# ORD_PT2399.net
KiCad netlist of a schematic drawn in Altium Designer
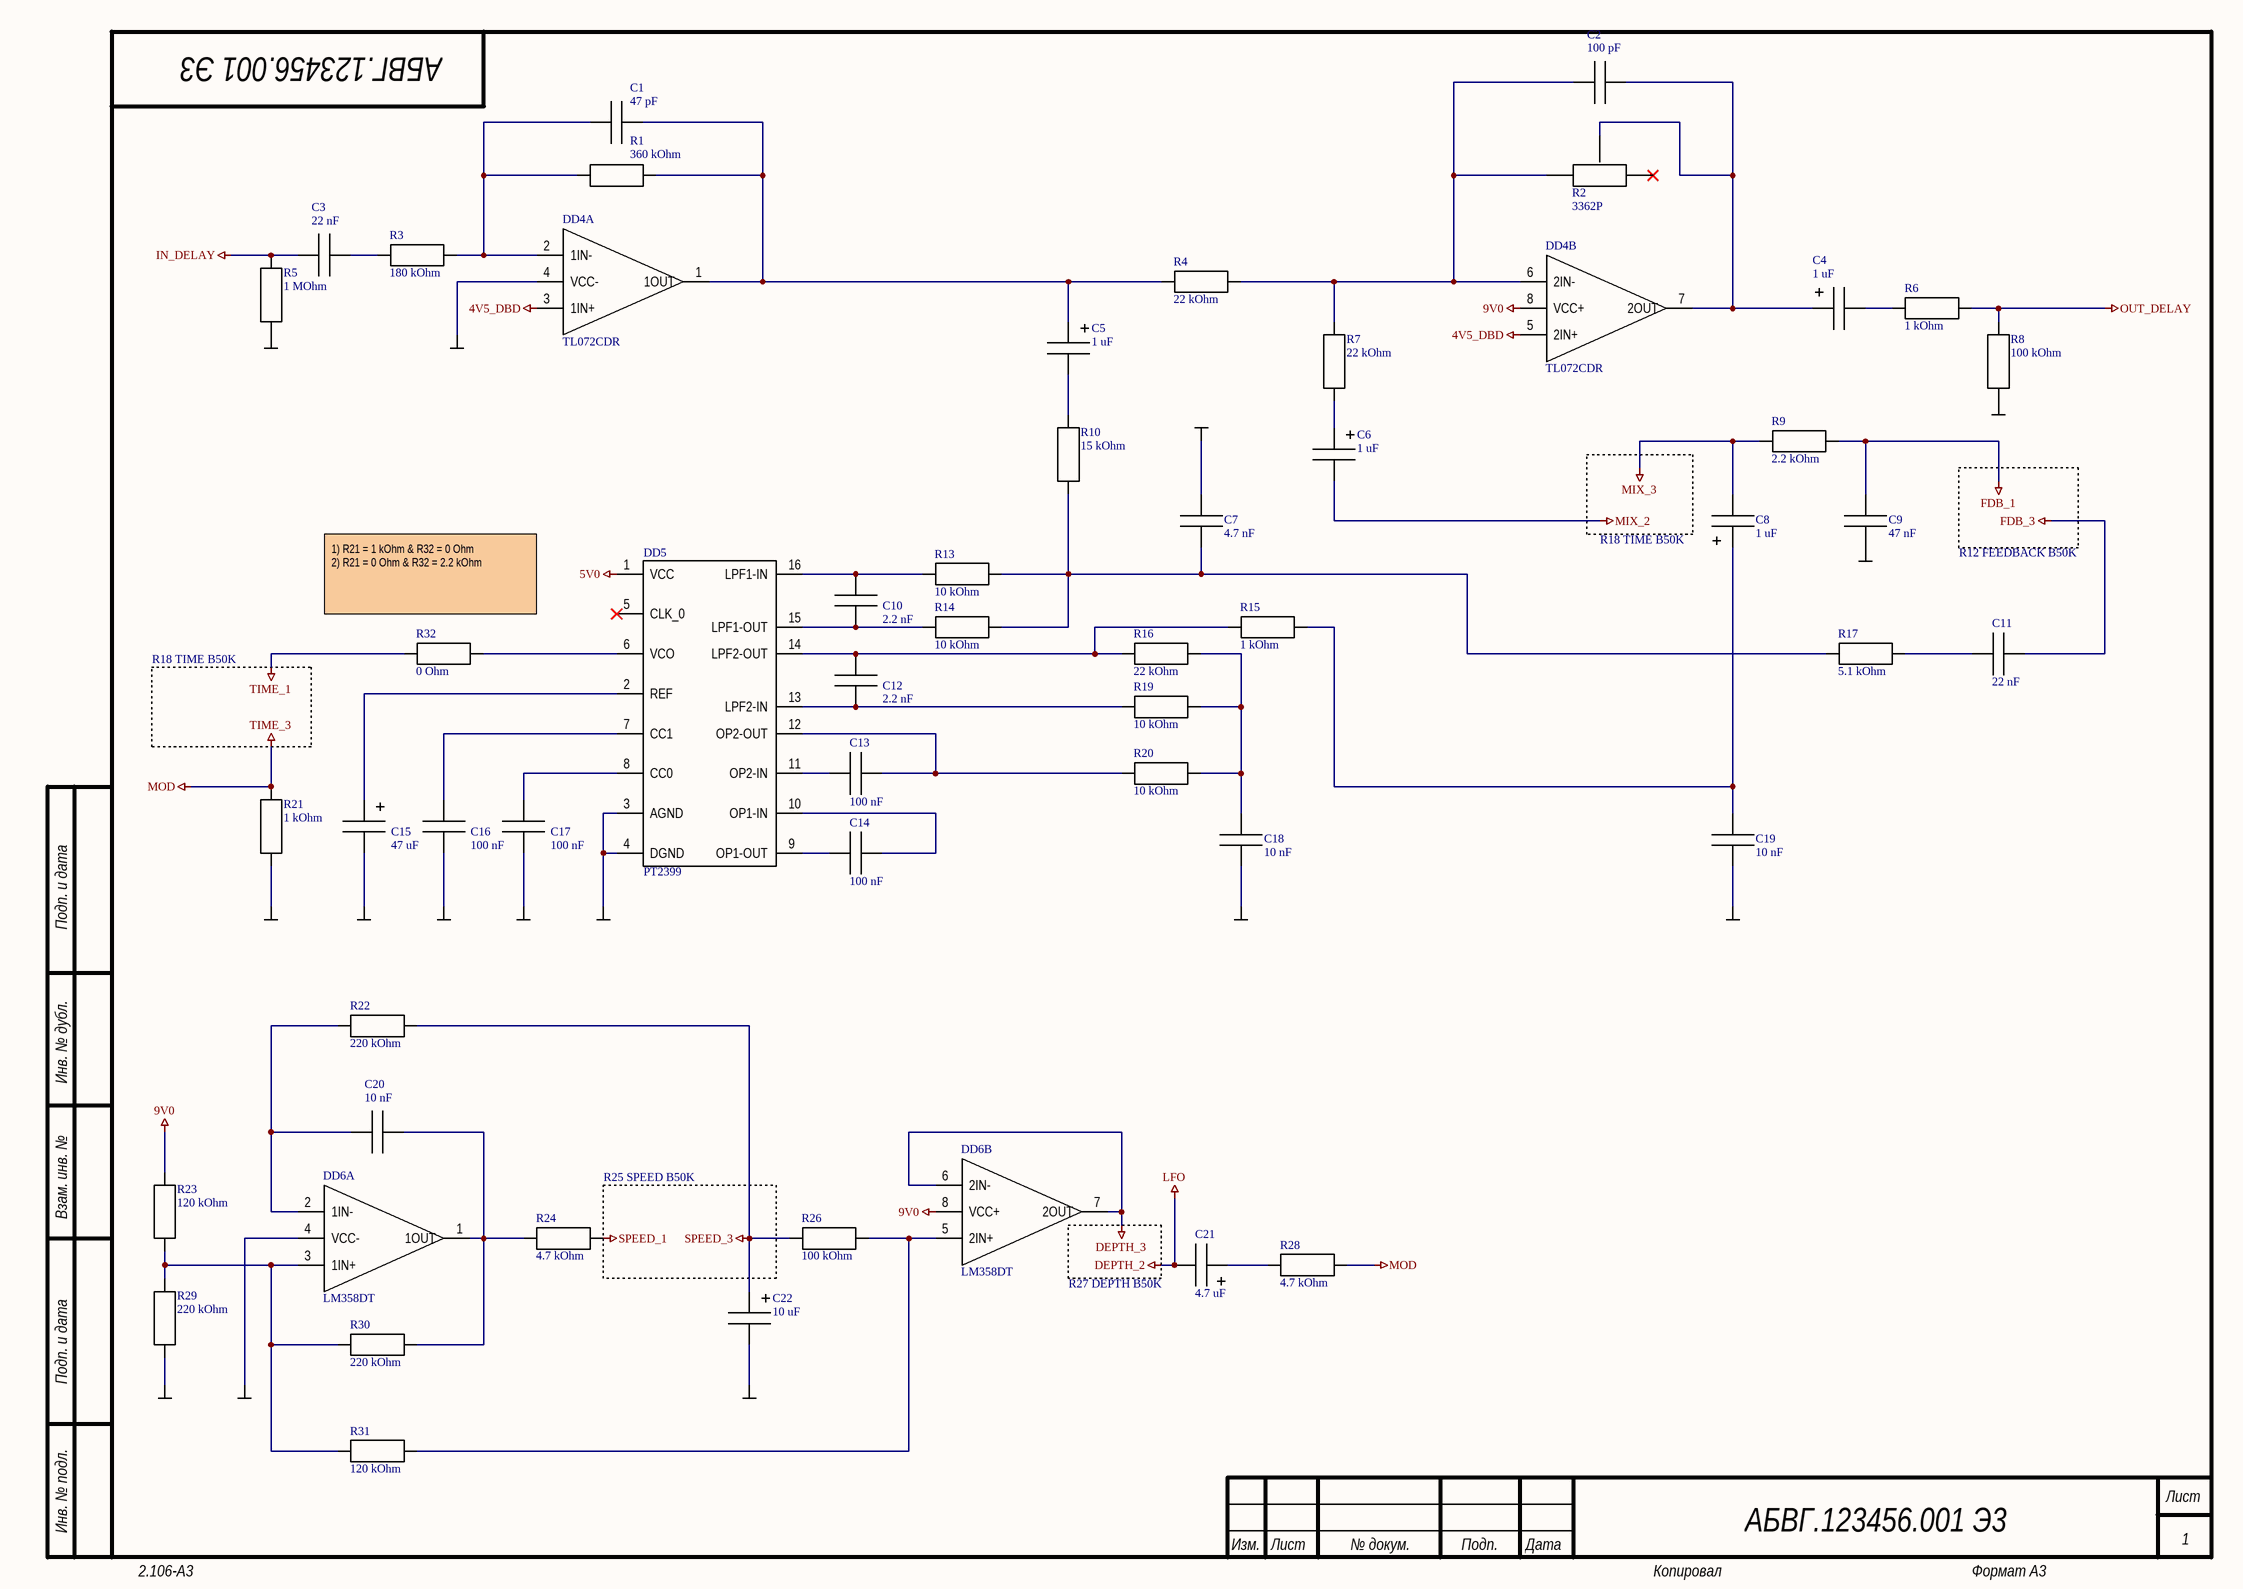
[diagram p0: ORD_PT2399.SchDoc]

(export (version "E")
  (design (tool "Eeschema 10.0.6"))
  (components
    (comp (ref "C1")
      (value "47 pF")
      (footprint "C0805[2012]")
      (libsource (lib "Gost_passive_lib") (part "Capacitor"))
    )
    (comp (ref "C2")
      (value "100 pF")
      (footprint "C0805[2012]")
      (libsource (lib "Gost_passive_lib") (part "Capacitor"))
    )
    (comp (ref "C3")
      (value "22 nF")
      (footprint "C0805[2012]")
      (libsource (lib "Gost_passive_lib") (part "Capacitor"))
    )
    (comp (ref "C4")
      (value "1 uF")
      (footprint "C3216_CASE-A")
      (libsource (lib "Gost_passive_lib") (part "Capacitor_Pol"))
    )
    (comp (ref "C5")
      (value "1 uF")
      (footprint "C3216_CASE-A")
      (libsource (lib "Gost_passive_lib") (part "Capacitor_Pol"))
    )
    (comp (ref "C6")
      (value "1 uF")
      (footprint "C3216_CASE-A")
      (libsource (lib "Gost_passive_lib") (part "Capacitor_Pol"))
    )
    (comp (ref "C7")
      (value "4.7 nF")
      (footprint "C0805[2012]")
      (libsource (lib "Gost_passive_lib") (part "Capacitor"))
    )
    (comp (ref "C8")
      (value "1 uF")
      (footprint "C3216_CASE-A")
      (libsource (lib "Gost_passive_lib") (part "Capacitor_Pol"))
    )
    (comp (ref "C9")
      (value "47 nF")
      (footprint "C0805[2012]")
      (libsource (lib "Gost_passive_lib") (part "Capacitor"))
    )
    (comp (ref "C10")
      (value "2.2 nF")
      (footprint "C0805[2012]")
      (libsource (lib "Gost_passive_lib") (part "Capacitor"))
    )
    (comp (ref "C11")
      (value "22 nF")
      (footprint "C0805[2012]")
      (libsource (lib "Gost_passive_lib") (part "Capacitor"))
    )
    (comp (ref "C12")
      (value "2.2 nF")
      (footprint "C0805[2012]")
      (libsource (lib "Gost_passive_lib") (part "Capacitor"))
    )
    (comp (ref "C13")
      (value "100 nF")
      (footprint "C0805[2012]")
      (libsource (lib "Gost_passive_lib") (part "Capacitor"))
    )
    (comp (ref "C14")
      (value "100 nF")
      (footprint "C0805[2012]")
      (libsource (lib "Gost_passive_lib") (part "Capacitor"))
    )
    (comp (ref "C15")
      (value "47 uF")
      (footprint "C3216_CASE-A")
      (libsource (lib "Gost_passive_lib") (part "Capacitor_Pol"))
    )
    (comp (ref "C16")
      (value "100 nF")
      (footprint "C0805[2012]")
      (libsource (lib "Gost_passive_lib") (part "Capacitor"))
    )
    (comp (ref "C17")
      (value "100 nF")
      (footprint "C0805[2012]")
      (libsource (lib "Gost_passive_lib") (part "Capacitor"))
    )
    (comp (ref "C18")
      (value "10 nF")
      (footprint "C0805[2012]")
      (libsource (lib "Gost_passive_lib") (part "Capacitor"))
    )
    (comp (ref "C19")
      (value "10 nF")
      (footprint "C0805[2012]")
      (libsource (lib "Gost_passive_lib") (part "Capacitor"))
    )
    (comp (ref "C20")
      (value "10 nF")
      (footprint "C0805[2012]")
      (libsource (lib "Gost_passive_lib") (part "Capacitor"))
    )
    (comp (ref "C21")
      (value "4.7 uF")
      (footprint "C3216_CASE-A")
      (libsource (lib "Gost_passive_lib") (part "Capacitor_Pol"))
    )
    (comp (ref "C22")
      (value "10 uF")
      (footprint "C3216_CASE-A")
      (libsource (lib "Gost_passive_lib") (part "Capacitor_Pol"))
    )
    (comp (ref "DD4")
      (value "TL072CDR")
      (footprint "SO8")
      (description "TL072CDR, Dual Operational Amplifier 4 MHz -18 to 18V, 8-Pin SO")
      (fields
        (field (name "MANUFACTURER_PART_NUMBER") "LM358DT")
        (field (name "MOUSER PART NUMBER") "511-LM358DT")
      )
      (libsource (lib "Gost_active_libs") (part "TL072CDR"))
    )
    (comp (ref "DD5")
      (value "PT2399")
      (footprint "DIP16_with_Socket")
      (description "Echo Processor IC")
      (libsource (lib "Gost_active_libs") (part "PT2399"))
    )
    (comp (ref "DD6")
      (value "LM358DT")
      (footprint "SO8")
      (description "LM358DT, Dual Operational Amplifier 1.1MHz 5 to 28V, 8-Pin SO")
      (fields (field (name "MOUSER PART NUMBER") "511-LM358DT") (field (name "RS PART NUMBER") "7140827P"))
      (libsource (lib "Gost_active_libs") (part "LM358DT"))
    )
    (comp (ref "R1")
      (value "360 kOhm")
      (footprint "R0805[2012]")
      (libsource (lib "Gost_passive_lib") (part "Resistor"))
    )
    (comp (ref "R2") (value "3362P") (footprint "3362p") (libsource (lib "Gost_passive_lib") (part "3362P")))
    (comp (ref "R3")
      (value "180 kOhm")
      (footprint "R0805[2012]")
      (libsource (lib "Gost_passive_lib") (part "Resistor"))
    )
    (comp (ref "R4")
      (value "22 kOhm")
      (footprint "R0805[2012]")
      (libsource (lib "Gost_passive_lib") (part "Resistor"))
    )
    (comp (ref "R5")
      (value "1 MOhm")
      (footprint "R0805[2012]")
      (libsource (lib "Gost_passive_lib") (part "Resistor"))
    )
    (comp (ref "R6")
      (value "1 kOhm")
      (footprint "R0805[2012]")
      (libsource (lib "Gost_passive_lib") (part "Resistor"))
    )
    (comp (ref "R7")
      (value "22 kOhm")
      (footprint "R0805[2012]")
      (libsource (lib "Gost_passive_lib") (part "Resistor"))
    )
    (comp (ref "R8")
      (value "100 kOhm")
      (footprint "R0805[2012]")
      (libsource (lib "Gost_passive_lib") (part "Resistor"))
    )
    (comp (ref "R9")
      (value "2.2 kOhm")
      (footprint "R0805[2012]")
      (libsource (lib "Gost_passive_lib") (part "Resistor"))
    )
    (comp (ref "R10")
      (value "15 kOhm")
      (footprint "R0805[2012]")
      (libsource (lib "Gost_passive_lib") (part "Resistor"))
    )
    (comp (ref "R13")
      (value "10 kOhm")
      (footprint "R0805[2012]")
      (libsource (lib "Gost_passive_lib") (part "Resistor"))
    )
    (comp (ref "R14")
      (value "10 kOhm")
      (footprint "R0805[2012]")
      (libsource (lib "Gost_passive_lib") (part "Resistor"))
    )
    (comp (ref "R15")
      (value "1 kOhm")
      (footprint "R0805[2012]")
      (libsource (lib "Gost_passive_lib") (part "Resistor"))
    )
    (comp (ref "R16")
      (value "22 kOhm")
      (footprint "R0805[2012]")
      (libsource (lib "Gost_passive_lib") (part "Resistor"))
    )
    (comp (ref "R17")
      (value "5.1 kOhm")
      (footprint "R0805[2012]")
      (libsource (lib "Gost_passive_lib") (part "Resistor"))
    )
    (comp (ref "R19")
      (value "10 kOhm")
      (footprint "R0805[2012]")
      (libsource (lib "Gost_passive_lib") (part "Resistor"))
    )
    (comp (ref "R20")
      (value "10 kOhm")
      (footprint "R0805[2012]")
      (libsource (lib "Gost_passive_lib") (part "Resistor"))
    )
    (comp (ref "R21")
      (value "1 kOhm")
      (footprint "R0805[2012]")
      (libsource (lib "Gost_passive_lib") (part "Resistor"))
    )
    (comp (ref "R22")
      (value "220 kOhm")
      (footprint "R0805[2012]")
      (libsource (lib "Gost_passive_lib") (part "Resistor"))
    )
    (comp (ref "R23")
      (value "120 kOhm")
      (footprint "R0805[2012]")
      (libsource (lib "Gost_passive_lib") (part "Resistor"))
    )
    (comp (ref "R24")
      (value "4.7 kOhm")
      (footprint "R0805[2012]")
      (libsource (lib "Gost_passive_lib") (part "Resistor"))
    )
    (comp (ref "R26")
      (value "100 kOhm")
      (footprint "R0805[2012]")
      (libsource (lib "Gost_passive_lib") (part "Resistor"))
    )
    (comp (ref "R28")
      (value "4.7 kOhm")
      (footprint "R0805[2012]")
      (libsource (lib "Gost_passive_lib") (part "Resistor"))
    )
    (comp (ref "R29")
      (value "220 kOhm")
      (footprint "R0805[2012]")
      (libsource (lib "Gost_passive_lib") (part "Resistor"))
    )
    (comp (ref "R30")
      (value "220 kOhm")
      (footprint "R0805[2012]")
      (libsource (lib "Gost_passive_lib") (part "Resistor"))
    )
    (comp (ref "R31")
      (value "120 kOhm")
      (footprint "R0805[2012]")
      (libsource (lib "Gost_passive_lib") (part "Resistor"))
    )
    (comp (ref "R32")
      (value "0 Ohm")
      (footprint "R0805[2012]")
      (libsource (lib "Gost_passive_lib") (part "Resistor"))
    )
  )
  (nets
    (net (code "1") (name "4V5_DBD") (class "Default")
      (node (ref "DD4") (pin "3") (pinfunction "1IN+_3") (pintype "passive"))
      (node (ref "DD4") (pin "5") (pinfunction "2IN+_5") (pintype "passive"))
    )
    (net (code "2") (name "5V0") (class "Default")
      (node (ref "DD5") (pin "1") (pinfunction "VCC_1") (pintype "power_in"))
    )
    (net (code "3") (name "9V0") (class "Default")
      (node (ref "DD4") (pin "8") (pinfunction "VCC+_8") (pintype "power_in"))
      (node (ref "DD6") (pin "8") (pinfunction "VCC+_8") (pintype "power_in"))
      (node (ref "R23") (pin "1") (pinfunction "1_1") (pintype "passive"))
    )
    (net (code "4") (name "DEPTH_2") (class "Default")
      (node (ref "C21") (pin "2") (pinfunction "2_2") (pintype "passive"))
    )
    (net (code "5") (name "DEPTH_3") (class "Default")
      (node (ref "DD6") (pin "6") (pinfunction "2IN-_6") (pintype "passive"))
      (node (ref "DD6") (pin "7") (pinfunction "2OUT_7") (pintype "passive"))
    )
    (net (code "6") (name "FDB_1") (class "Default")
      (node (ref "C9") (pin "1") (pinfunction "1_1") (pintype "passive"))
      (node (ref "R9") (pin "2") (pinfunction "2_2") (pintype "passive"))
    )
    (net (code "7") (name "FDB_3") (class "Default")
      (node (ref "C11") (pin "2") (pinfunction "2_2") (pintype "passive"))
    )
    (net (code "8") (name "GND") (class "Default")
      (node (ref "C15") (pin "2") (pinfunction "2_2") (pintype "passive"))
      (node (ref "C16") (pin "1") (pinfunction "1_1") (pintype "passive"))
      (node (ref "C17") (pin "1") (pinfunction "1_1") (pintype "passive"))
      (node (ref "C18") (pin "2") (pinfunction "2_2") (pintype "passive"))
      (node (ref "C19") (pin "2") (pinfunction "2_2") (pintype "passive"))
      (node (ref "C22") (pin "2") (pinfunction "2_2") (pintype "passive"))
      (node (ref "C7") (pin "1") (pinfunction "1_1") (pintype "passive"))
      (node (ref "C9") (pin "2") (pinfunction "2_2") (pintype "passive"))
      (node (ref "DD4") (pin "4") (pinfunction "VCC-_4") (pintype "power_in"))
      (node (ref "DD5") (pin "3") (pinfunction "AGND_3") (pintype "passive"))
      (node (ref "DD5") (pin "4") (pinfunction "DGND_4") (pintype "passive"))
      (node (ref "DD6") (pin "4") (pinfunction "VCC-_4") (pintype "power_in"))
      (node (ref "R21") (pin "1") (pinfunction "1_1") (pintype "passive"))
      (node (ref "R29") (pin "2") (pinfunction "2_2") (pintype "passive"))
      (node (ref "R5") (pin "1") (pinfunction "1_1") (pintype "passive"))
      (node (ref "R8") (pin "2") (pinfunction "2_2") (pintype "passive"))
    )
    (net (code "9") (name "IN_DELAY") (class "Default")
      (node (ref "C3") (pin "1") (pinfunction "1_1") (pintype "passive"))
      (node (ref "R5") (pin "2") (pinfunction "2_2") (pintype "passive"))
    )
    (net (code "10") (name "MIX_2") (class "Default")
      (node (ref "C6") (pin "2") (pinfunction "2_2") (pintype "passive"))
    )
    (net (code "11") (name "MIX_3") (class "Default")
      (node (ref "C8") (pin "2") (pinfunction "2_2") (pintype "passive"))
      (node (ref "R9") (pin "1") (pinfunction "1_1") (pintype "passive"))
    )
    (net (code "12") (name "MOD") (class "Default")
      (node (ref "R21") (pin "2") (pinfunction "2_2") (pintype "passive"))
      (node (ref "R28") (pin "2") (pinfunction "2_2") (pintype "passive"))
    )
    (net (code "13") (name "Net-(C3-Pad2)") (class "Default")
      (node (ref "C3") (pin "2") (pinfunction "2_2") (pintype "passive"))
      (node (ref "R3") (pin "2") (pinfunction "2_2") (pintype "passive"))
    )
    (net (code "14") (name "Net-(C4-Pad2)") (class "Default")
      (node (ref "C4") (pin "2") (pinfunction "2_2") (pintype "passive"))
      (node (ref "R6") (pin "2") (pinfunction "2_2") (pintype "passive"))
    )
    (net (code "15") (name "Net-(C5-Pad2)") (class "Default")
      (node (ref "C5") (pin "2") (pinfunction "2_2") (pintype "passive"))
      (node (ref "R10") (pin "1") (pinfunction "1_1") (pintype "passive"))
    )
    (net (code "16") (name "Net-(C6-Pad1)") (class "Default")
      (node (ref "C6") (pin "1") (pinfunction "1_1") (pintype "passive"))
      (node (ref "R7") (pin "2") (pinfunction "2_2") (pintype "passive"))
    )
    (net (code "17") (name "Net-(C7-Pad2)") (class "Default")
      (node (ref "C7") (pin "2") (pinfunction "2_2") (pintype "passive"))
      (node (ref "R10") (pin "2") (pinfunction "2_2") (pintype "passive"))
      (node (ref "R13") (pin "2") (pinfunction "2_2") (pintype "passive"))
      (node (ref "R14") (pin "2") (pinfunction "2_2") (pintype "passive"))
      (node (ref "R17") (pin "1") (pinfunction "1_1") (pintype "passive"))
    )
    (net (code "18") (name "Net-(C11-Pad1)") (class "Default")
      (node (ref "C11") (pin "1") (pinfunction "1_1") (pintype "passive"))
      (node (ref "R17") (pin "2") (pinfunction "2_2") (pintype "passive"))
    )
    (net (code "19") (name "Net-(C18-Pad1)") (class "Default")
      (node (ref "C18") (pin "1") (pinfunction "1_1") (pintype "passive"))
      (node (ref "R16") (pin "2") (pinfunction "2_2") (pintype "passive"))
      (node (ref "R19") (pin "2") (pinfunction "2_2") (pintype "passive"))
      (node (ref "R20") (pin "2") (pinfunction "2_2") (pintype "passive"))
    )
    (net (code "20") (name "Net-(C19-Pad1)") (class "Default")
      (node (ref "C19") (pin "1") (pinfunction "1_1") (pintype "passive"))
      (node (ref "C8") (pin "1") (pinfunction "1_1") (pintype "passive"))
      (node (ref "R15") (pin "2") (pinfunction "2_2") (pintype "passive"))
    )
    (net (code "21") (name "Net-(C21-Pad1)") (class "Default")
      (node (ref "C21") (pin "1") (pinfunction "1_1") (pintype "passive"))
      (node (ref "R28") (pin "1") (pinfunction "1_1") (pintype "passive"))
    )
    (net (code "22") (name "Net-(DD4A-1IN-)") (class "Default")
      (node (ref "C1") (pin "1") (pinfunction "1_1") (pintype "passive"))
      (node (ref "DD4") (pin "2") (pinfunction "1IN-_2") (pintype "passive"))
      (node (ref "R1") (pin "2") (pinfunction "2_2") (pintype "passive"))
      (node (ref "R3") (pin "1") (pinfunction "1_1") (pintype "passive"))
    )
    (net (code "23") (name "Net-(DD4A-1OUT)") (class "Default")
      (node (ref "C1") (pin "2") (pinfunction "2_2") (pintype "passive"))
      (node (ref "C5") (pin "1") (pinfunction "1_1") (pintype "passive"))
      (node (ref "DD4") (pin "1") (pinfunction "1OUT_1") (pintype "passive"))
      (node (ref "R1") (pin "1") (pinfunction "1_1") (pintype "passive"))
      (node (ref "R4") (pin "2") (pinfunction "2_2") (pintype "passive"))
    )
    (net (code "24") (name "Net-(DD4B-2IN-)") (class "Default")
      (node (ref "C2") (pin "1") (pinfunction "1_1") (pintype "passive"))
      (node (ref "DD4") (pin "6") (pinfunction "2IN-_6") (pintype "passive"))
      (node (ref "R2") (pin "1") (pinfunction "1_1") (pintype "passive"))
      (node (ref "R4") (pin "1") (pinfunction "1_1") (pintype "passive"))
      (node (ref "R7") (pin "1") (pinfunction "1_1") (pintype "passive"))
    )
    (net (code "25") (name "Net-(DD4B-2OUT)") (class "Default")
      (node (ref "C2") (pin "2") (pinfunction "2_2") (pintype "passive"))
      (node (ref "C4") (pin "1") (pinfunction "1_1") (pintype "passive"))
      (node (ref "DD4") (pin "7") (pinfunction "2OUT_7") (pintype "passive"))
      (node (ref "R2") (pin "2") (pinfunction "2_2") (pintype "passive"))
    )
    (net (code "26") (name "Net-(DD5-CC0)") (class "Default")
      (node (ref "C17") (pin "2") (pinfunction "2_2") (pintype "passive"))
      (node (ref "DD5") (pin "8") (pinfunction "CC0_8") (pintype "passive"))
    )
    (net (code "27") (name "Net-(DD5-CC1)") (class "Default")
      (node (ref "C16") (pin "2") (pinfunction "2_2") (pintype "passive"))
      (node (ref "DD5") (pin "7") (pinfunction "CC1_7") (pintype "passive"))
    )
    (net (code "28") (name "Net-(DD5-LPF1-IN)") (class "Default")
      (node (ref "C10") (pin "2") (pinfunction "2_2") (pintype "passive"))
      (node (ref "DD5") (pin "16") (pinfunction "LPF1-IN_16") (pintype "passive"))
      (node (ref "R13") (pin "1") (pinfunction "1_1") (pintype "passive"))
    )
    (net (code "29") (name "Net-(DD5-LPF1-OUT)") (class "Default")
      (node (ref "C10") (pin "1") (pinfunction "1_1") (pintype "passive"))
      (node (ref "DD5") (pin "15") (pinfunction "LPF1-OUT_15") (pintype "passive"))
      (node (ref "R14") (pin "1") (pinfunction "1_1") (pintype "passive"))
    )
    (net (code "30") (name "Net-(DD5-LPF2-IN)") (class "Default")
      (node (ref "C12") (pin "1") (pinfunction "1_1") (pintype "passive"))
      (node (ref "DD5") (pin "13") (pinfunction "LPF2-IN_13") (pintype "passive"))
      (node (ref "R19") (pin "1") (pinfunction "1_1") (pintype "passive"))
    )
    (net (code "31") (name "Net-(DD5-LPF2-OUT)") (class "Default")
      (node (ref "C12") (pin "2") (pinfunction "2_2") (pintype "passive"))
      (node (ref "DD5") (pin "14") (pinfunction "LPF2-OUT_14") (pintype "passive"))
      (node (ref "R15") (pin "1") (pinfunction "1_1") (pintype "passive"))
      (node (ref "R16") (pin "1") (pinfunction "1_1") (pintype "passive"))
    )
    (net (code "32") (name "Net-(DD5-OP1-IN)") (class "Default")
      (node (ref "C14") (pin "1") (pinfunction "1_1") (pintype "passive"))
      (node (ref "DD5") (pin "10") (pinfunction "OP1-IN_10") (pintype "passive"))
    )
    (net (code "33") (name "Net-(DD5-OP1-OUT)") (class "Default")
      (node (ref "C14") (pin "2") (pinfunction "2_2") (pintype "passive"))
      (node (ref "DD5") (pin "9") (pinfunction "OP1-OUT_9") (pintype "passive"))
    )
    (net (code "34") (name "Net-(DD5-OP2-IN)") (class "Default")
      (node (ref "C13") (pin "2") (pinfunction "2_2") (pintype "passive"))
      (node (ref "DD5") (pin "11") (pinfunction "OP2-IN_11") (pintype "passive"))
    )
    (net (code "35") (name "Net-(DD5-OP2-OUT)") (class "Default")
      (node (ref "C13") (pin "1") (pinfunction "1_1") (pintype "passive"))
      (node (ref "DD5") (pin "12") (pinfunction "OP2-OUT_12") (pintype "passive"))
      (node (ref "R20") (pin "1") (pinfunction "1_1") (pintype "passive"))
    )
    (net (code "36") (name "Net-(DD5-REF)") (class "Default")
      (node (ref "C15") (pin "1") (pinfunction "1_1") (pintype "passive"))
      (node (ref "DD5") (pin "2") (pinfunction "REF_2") (pintype "passive"))
    )
    (net (code "37") (name "Net-(DD5-VCO)") (class "Default")
      (node (ref "DD5") (pin "6") (pinfunction "VCO_6") (pintype "passive"))
      (node (ref "R32") (pin "1") (pinfunction "1_1") (pintype "passive"))
    )
    (net (code "38") (name "Net-(DD6A-1IN+)") (class "Default")
      (node (ref "DD6") (pin "3") (pinfunction "1IN+_3") (pintype "passive"))
      (node (ref "R23") (pin "2") (pinfunction "2_2") (pintype "passive"))
      (node (ref "R29") (pin "1") (pinfunction "1_1") (pintype "passive"))
      (node (ref "R30") (pin "1") (pinfunction "1_1") (pintype "passive"))
      (node (ref "R31") (pin "1") (pinfunction "1_1") (pintype "passive"))
    )
    (net (code "39") (name "Net-(DD6A-1IN-)") (class "Default")
      (node (ref "C20") (pin "1") (pinfunction "1_1") (pintype "passive"))
      (node (ref "DD6") (pin "2") (pinfunction "1IN-_2") (pintype "passive"))
      (node (ref "R22") (pin "1") (pinfunction "1_1") (pintype "passive"))
    )
    (net (code "40") (name "Net-(DD6A-1OUT)") (class "Default")
      (node (ref "C20") (pin "2") (pinfunction "2_2") (pintype "passive"))
      (node (ref "DD6") (pin "1") (pinfunction "1OUT_1") (pintype "passive"))
      (node (ref "R24") (pin "1") (pinfunction "1_1") (pintype "passive"))
      (node (ref "R30") (pin "2") (pinfunction "2_2") (pintype "passive"))
    )
    (net (code "41") (name "Net-(DD6B-2IN+)") (class "Default")
      (node (ref "DD6") (pin "5") (pinfunction "2IN+_5") (pintype "passive"))
      (node (ref "R26") (pin "2") (pinfunction "2_2") (pintype "passive"))
      (node (ref "R31") (pin "2") (pinfunction "2_2") (pintype "passive"))
    )
    (net (code "42") (name "OUT_DELAY") (class "Default")
      (node (ref "R6") (pin "1") (pinfunction "1_1") (pintype "passive"))
      (node (ref "R8") (pin "1") (pinfunction "1_1") (pintype "passive"))
    )
    (net (code "43") (name "SPEED_1") (class "Default")
      (node (ref "R24") (pin "2") (pinfunction "2_2") (pintype "passive"))
    )
    (net (code "44") (name "SPEED_3") (class "Default")
      (node (ref "C22") (pin "1") (pinfunction "1_1") (pintype "passive"))
      (node (ref "R22") (pin "2") (pinfunction "2_2") (pintype "passive"))
      (node (ref "R26") (pin "1") (pinfunction "1_1") (pintype "passive"))
    )
    (net (code "45") (name "TIME_1") (class "Default")
      (node (ref "R32") (pin "2") (pinfunction "2_2") (pintype "passive"))
    )
    (net (code "46") (name "unconnected-(DD5-CLK_0-Pad5)") (class "Default")
      (node (ref "DD5") (pin "5") (pinfunction "CLK_0_5") (pintype "passive+no_connect"))
    )
    (net (code "47") (name "unconnected-(R2-Pad3)") (class "Default")
      (node (ref "R2") (pin "3") (pinfunction "3_3") (pintype "passive+no_connect"))
    )
  )
)
